# Sheet1.net
KiCad netlist of a schematic drawn in Altium Designer
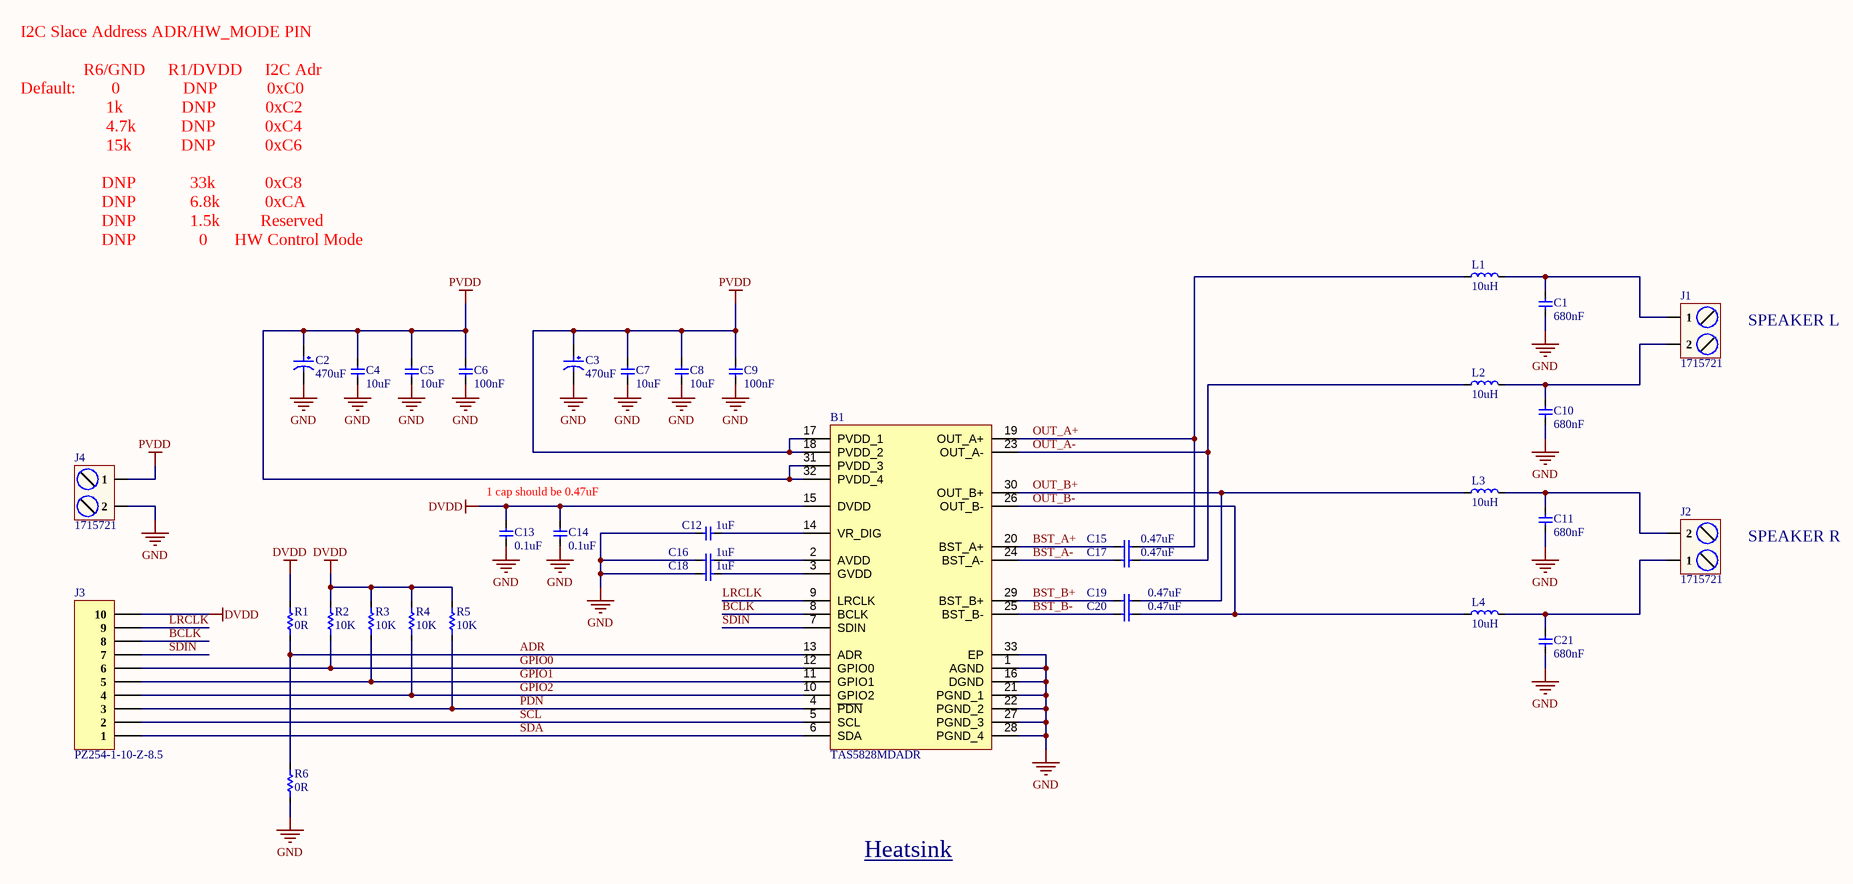
[diagram p0: Sheet1.SchDoc]

(export (version "E")
  (design (tool "Eeschema 10.0.6"))
  (components
    (comp (ref "B1")
      (value "TAS5828MDADR")
      (footprint "SOP65P810X115-33M")
      (fields
        (field (name "MOUSER PART NUMBER") "595-TAS5828MDADR")
        (field (name "LCSC PART NUMBER") "C5214953")
      )
      (libsource (lib "Schlib") (part "TAS5828MDADR"))
    )
    (comp (ref "C1")
      (value "680nF")
      (footprint "Cap-0805")
      (description "50V 680nF X7R ±10% 0805 Multilayer Ceramic Capacitors MLCC - SMD/SMT ROHS")
      (fields
        (field (name "MANUFACTURER") "YAGEO")
        (field (name "MANUFACTURER PART NUMBER") "CC0805KKX7R9BB684")
      )
      (libsource (lib "Schlib") (part "CC0805KKX7R9BB684"))
    )
    (comp (ref "C2")
      (value "470uF")
      (footprint "RVT470UF50V34RV0133")
      (description "470uF 50V 50mA@120Hz ±20% SMD,D12.5xL13.5mm Aluminum Electrolytic Capacitors - SMD ROHS")
      (fields (field (name "LCSC PART NUMBER") "C2837182") (field (name "MANUFACTURER") "KNSCHA"))
      (libsource (lib "Schlib") (part "RVT470UF50V34RV0133"))
    )
    (comp (ref "C3")
      (value "470uF")
      (footprint "RVT470UF50V34RV0133")
      (description "470uF 50V 50mA@120Hz ±20% SMD,D12.5xL13.5mm Aluminum Electrolytic Capacitors - SMD ROHS")
      (fields (field (name "LCSC PART NUMBER") "C2837182") (field (name "MANUFACTURER") "KNSCHA"))
      (libsource (lib "Schlib") (part "RVT470UF50V34RV0133"))
    )
    (comp (ref "C4")
      (value "10uF")
      (footprint "Cap-0805")
      (description "CAP CER 10UF 50V X5R 0805")
      (fields
        (field (name "MANUFACTURER") "Murata")
        (field (name "MANUFACTURER PART NUMBER") "GRM21BR61H106ME43L")
      )
      (libsource (lib "eSpark Libraries") (part "GRM21BR61H106ME43L"))
    )
    (comp (ref "C5")
      (value "10uF")
      (footprint "Cap-0805")
      (description "CAP CER 10UF 50V X5R 0805")
      (fields
        (field (name "MANUFACTURER") "Murata")
        (field (name "MANUFACTURER PART NUMBER") "GRM21BR61H106ME43L")
      )
      (libsource (lib "eSpark Libraries") (part "GRM21BR61H106ME43L"))
    )
    (comp (ref "C6")
      (value "100nF")
      (footprint "Cap-0603")
      (description "CAP CER 0.1UF 50V X5R 0603")
      (fields
        (field (name "MANUFACTURER") "Yageo")
        (field (name "MANUFACTURER PART NUMBER") "CC0603KRX5R9BB104")
      )
      (libsource (lib "Schlib") (part "CC0603KRX5R9BB104"))
    )
    (comp (ref "C7")
      (value "10uF")
      (footprint "Cap-0805")
      (description "CAP CER 10UF 50V X5R 0805")
      (fields
        (field (name "MANUFACTURER") "Murata")
        (field (name "MANUFACTURER PART NUMBER") "GRM21BR61H106ME43L")
      )
      (libsource (lib "eSpark Libraries") (part "GRM21BR61H106ME43L"))
    )
    (comp (ref "C8")
      (value "10uF")
      (footprint "Cap-0805")
      (description "CAP CER 10UF 50V X5R 0805")
      (fields
        (field (name "MANUFACTURER") "Murata")
        (field (name "MANUFACTURER PART NUMBER") "GRM21BR61H106ME43L")
      )
      (libsource (lib "eSpark Libraries") (part "GRM21BR61H106ME43L"))
    )
    (comp (ref "C9")
      (value "100nF")
      (footprint "Cap-0603")
      (description "CAP CER 0.1UF 50V X5R 0603")
      (fields
        (field (name "MANUFACTURER") "Yageo")
        (field (name "MANUFACTURER PART NUMBER") "CC0603KRX5R9BB104")
      )
      (libsource (lib "Schlib") (part "CC0603KRX5R9BB104"))
    )
    (comp (ref "C10")
      (value "680nF")
      (footprint "Cap-0805")
      (description "50V 680nF X7R ±10% 0805 Multilayer Ceramic Capacitors MLCC - SMD/SMT ROHS")
      (fields
        (field (name "MANUFACTURER") "YAGEO")
        (field (name "MANUFACTURER PART NUMBER") "CC0805KKX7R9BB684")
      )
      (libsource (lib "Schlib") (part "CC0805KKX7R9BB684"))
    )
    (comp (ref "C11")
      (value "680nF")
      (footprint "Cap-0805")
      (description "50V 680nF X7R ±10% 0805 Multilayer Ceramic Capacitors MLCC - SMD/SMT ROHS")
      (fields
        (field (name "MANUFACTURER") "YAGEO")
        (field (name "MANUFACTURER PART NUMBER") "CC0805KKX7R9BB684")
      )
      (libsource (lib "Schlib") (part "CC0805KKX7R9BB684"))
    )
    (comp (ref "C12")
      (value "1uF")
      (footprint "Cap-0603")
      (description "CAP CER 1UF 25V X5R 0603")
      (fields
        (field (name "MANUFACTURER") "Yageo")
        (field (name "MANUFACTURER PART NUMBER") "CC0603KRX5R8BB105")
      )
      (libsource (lib "Schlib") (part "CC0603KRX5R8BB105"))
    )
    (comp (ref "C13")
      (value "0.1uF")
      (footprint "Cap-0402")
      (description "CAP CER 0.1UF 16V X7R 0402")
      (fields
        (field (name "MANUFACTURER") "Yageo")
        (field (name "MANUFACTURER PART NUMBER") "CC0402JRX7R7BB104")
      )
      (libsource (lib "Schlib") (part "CC0402JRX7R7BB104"))
    )
    (comp (ref "C14")
      (value "0.1uF")
      (footprint "Cap-0402")
      (description "CAP CER 0.1UF 16V X7R 0402")
      (fields
        (field (name "MANUFACTURER") "Yageo")
        (field (name "MANUFACTURER PART NUMBER") "CC0402JRX7R7BB104")
      )
      (libsource (lib "Schlib") (part "CC0402JRX7R7BB104"))
    )
    (comp (ref "C15")
      (value "0.47uF")
      (footprint "Cap-0603")
      (description "CAP CER 0.47UF 50V X5R 0603")
      (fields
        (field (name "MANUFACTURER") "Yageo")
        (field (name "MANUFACTURER PART NUMBER") "CC0603KRX5R9BB474")
      )
      (libsource (lib "Schlib") (part "CC0603KRX5R9BB474"))
    )
    (comp (ref "C16")
      (value "1uF")
      (footprint "Cap-0603")
      (description "CAP CER 1UF 25V X5R 0603")
      (fields
        (field (name "MANUFACTURER") "Yageo")
        (field (name "MANUFACTURER PART NUMBER") "CC0603KRX5R8BB105")
      )
      (libsource (lib "Schlib") (part "CC0603KRX5R8BB105"))
    )
    (comp (ref "C17")
      (value "0.47uF")
      (footprint "Cap-0603")
      (description "CAP CER 0.47UF 50V X5R 0603")
      (fields
        (field (name "MANUFACTURER") "Yageo")
        (field (name "MANUFACTURER PART NUMBER") "CC0603KRX5R9BB474")
      )
      (libsource (lib "Schlib") (part "CC0603KRX5R9BB474"))
    )
    (comp (ref "C18")
      (value "1uF")
      (footprint "Cap-0603")
      (description "CAP CER 1UF 25V X5R 0603")
      (fields
        (field (name "MANUFACTURER") "Yageo")
        (field (name "MANUFACTURER PART NUMBER") "CC0603KRX5R8BB105")
      )
      (libsource (lib "Schlib") (part "CC0603KRX5R8BB105"))
    )
    (comp (ref "C19")
      (value "0.47uF")
      (footprint "Cap-0603")
      (description "CAP CER 0.47UF 50V X5R 0603")
      (fields
        (field (name "MANUFACTURER") "Yageo")
        (field (name "MANUFACTURER PART NUMBER") "CC0603KRX5R9BB474")
      )
      (libsource (lib "Schlib") (part "CC0603KRX5R9BB474"))
    )
    (comp (ref "C20")
      (value "0.47uF")
      (footprint "Cap-0603")
      (description "CAP CER 0.47UF 50V X5R 0603")
      (fields
        (field (name "MANUFACTURER") "Yageo")
        (field (name "MANUFACTURER PART NUMBER") "CC0603KRX5R9BB474")
      )
      (libsource (lib "Schlib") (part "CC0603KRX5R9BB474"))
    )
    (comp (ref "C21")
      (value "680nF")
      (footprint "Cap-0805")
      (description "50V 680nF X7R ±10% 0805 Multilayer Ceramic Capacitors MLCC - SMD/SMT ROHS")
      (fields
        (field (name "MANUFACTURER") "YAGEO")
        (field (name "MANUFACTURER PART NUMBER") "CC0805KKX7R9BB684")
      )
      (libsource (lib "Schlib") (part "CC0805KKX7R9BB684"))
    )
    (comp (ref "J1")
      (value "1715721")
      (footprint "1715721")
      (description "TERM BLK 2P SIDE ENT 5.08MM PCB")
      (fields (field (name "MANUFACTURER") "Phoenix Contact") (field (name "LCSC PART NUMBER") "C480516"))
      (libsource (lib "") (part "1715721_1"))
    )
    (comp (ref "J2")
      (value "1715721")
      (footprint "1715721")
      (description "TERM BLK 2P SIDE ENT 5.08MM PCB")
      (fields (field (name "MANUFACTURER") "Phoenix Contact") (field (name "LCSC PART NUMBER") "C480516"))
      (libsource (lib "Schlib") (part "1715721"))
    )
    (comp (ref "J3")
      (value "PZ254-1-10-Z-8.5")
      (footprint "PZ254-1-10-Z-8.5")
      (fields (field (name "MANUFACTURER") "HCTL") (field (name "LCSC PART NUMBER") "C2894933"))
      (libsource (lib "Schlib") (part "PZ254-1-10-Z-8.5"))
    )
    (comp (ref "J4")
      (value "1715721")
      (footprint "1715721")
      (description "TERM BLK 2P SIDE ENT 5.08MM PCB")
      (fields (field (name "MANUFACTURER") "Phoenix Contact") (field (name "LCSC PART NUMBER") "C480516"))
      (libsource (lib "") (part "1715721_2"))
    )
    (comp (ref "L1")
      (value "10uH")
      (footprint "PSPMAA1040-100M-ANP")
      (description "7A 10uH ±20% 10A SMD,10.3x10.5mm Power Inductors ROHS")
      (fields
        (field (name "MANUFACTURER") "PROD Tech")
        (field (name "MANUFACTURER PART NUMBER") "PSPMAA1040-100M-ANP")
      )
      (libsource (lib "Schlib") (part "PSPMAA1040-100M-ANP"))
    )
    (comp (ref "L2")
      (value "10uH")
      (footprint "PSPMAA1040-100M-ANP")
      (description "7A 10uH ±20% 10A SMD,10.3x10.5mm Power Inductors ROHS")
      (fields
        (field (name "MANUFACTURER") "PROD Tech")
        (field (name "MANUFACTURER PART NUMBER") "PSPMAA1040-100M-ANP")
      )
      (libsource (lib "Schlib") (part "PSPMAA1040-100M-ANP"))
    )
    (comp (ref "L3")
      (value "10uH")
      (footprint "PSPMAA1040-100M-ANP")
      (description "7A 10uH ±20% 10A SMD,10.3x10.5mm Power Inductors ROHS")
      (fields
        (field (name "MANUFACTURER") "PROD Tech")
        (field (name "MANUFACTURER PART NUMBER") "PSPMAA1040-100M-ANP")
      )
      (libsource (lib "Schlib") (part "PSPMAA1040-100M-ANP"))
    )
    (comp (ref "L4")
      (value "10uH")
      (footprint "PSPMAA1040-100M-ANP")
      (description "7A 10uH ±20% 10A SMD,10.3x10.5mm Power Inductors ROHS")
      (fields
        (field (name "MANUFACTURER") "PROD Tech")
        (field (name "MANUFACTURER PART NUMBER") "PSPMAA1040-100M-ANP")
      )
      (libsource (lib "Schlib") (part "PSPMAA1040-100M-ANP"))
    )
    (comp (ref "R1")
      (value "0R")
      (footprint "Res-0402")
      (description "RES 0 OHM JUMPER 1/16W 0402")
      (fields
        (field (name "MANUFACTURER") "Yageo")
        (field (name "MANUFACTURER PART NUMBER") "RC0402FR-070RL")
      )
      (libsource (lib "Schlib") (part "RC0402FR-070RL"))
    )
    (comp (ref "R2")
      (value "10K")
      (footprint "Res-0402")
      (description "RES 10K OHM 1% 1/16W 0402")
      (fields
        (field (name "MANUFACTURER") "Yageo")
        (field (name "MANUFACTURER PART NUMBER") "RC0402FR-0710KL")
      )
      (libsource (lib "Schlib") (part "RC0402FR-0710KL"))
    )
    (comp (ref "R3")
      (value "10K")
      (footprint "Res-0402")
      (description "RES 10K OHM 1% 1/16W 0402")
      (fields
        (field (name "MANUFACTURER") "Yageo")
        (field (name "MANUFACTURER PART NUMBER") "RC0402FR-0710KL")
      )
      (libsource (lib "Schlib") (part "RC0402FR-0710KL"))
    )
    (comp (ref "R4")
      (value "10K")
      (footprint "Res-0402")
      (description "RES 10K OHM 1% 1/16W 0402")
      (fields
        (field (name "MANUFACTURER") "Yageo")
        (field (name "MANUFACTURER PART NUMBER") "RC0402FR-0710KL")
      )
      (libsource (lib "Schlib") (part "RC0402FR-0710KL"))
    )
    (comp (ref "R5")
      (value "10K")
      (footprint "Res-0402")
      (description "RES 10K OHM 1% 1/16W 0402")
      (fields
        (field (name "MANUFACTURER") "Yageo")
        (field (name "MANUFACTURER PART NUMBER") "RC0402FR-0710KL")
      )
      (libsource (lib "Schlib") (part "RC0402FR-0710KL"))
    )
    (comp (ref "R6")
      (value "0R")
      (footprint "Res-0402")
      (description "RES 0 OHM JUMPER 1/16W 0402")
      (fields
        (field (name "MANUFACTURER") "Yageo")
        (field (name "MANUFACTURER PART NUMBER") "RC0402FR-070RL")
      )
      (libsource (lib "Schlib") (part "RC0402FR-070RL"))
    )
  )
  (nets
    (net (code "1") (name "/ADR") (class "Default")
      (node (ref "B1") (pin "13") (pinfunction "ADR_13") (pintype "passive"))
      (node (ref "R1") (pin "1") (pinfunction "1_1") (pintype "passive"))
      (node (ref "R6") (pin "2") (pinfunction "2_2") (pintype "passive"))
    )
    (net (code "2") (name "/BCLK") (class "Default")
      (node (ref "B1") (pin "8") (pinfunction "BCLK_8") (pintype "passive"))
      (node (ref "J3") (pin "8") (pinfunction "8_8") (pintype "passive"))
    )
    (net (code "3") (name "/BST_A+") (class "Default")
      (node (ref "B1") (pin "20") (pinfunction "BST_A+_20") (pintype "passive"))
      (node (ref "C15") (pin "1") (pinfunction "1_1") (pintype "passive"))
    )
    (net (code "4") (name "/BST_A-") (class "Default")
      (node (ref "B1") (pin "24") (pinfunction "BST_A-_24") (pintype "passive"))
      (node (ref "C17") (pin "1") (pinfunction "1_1") (pintype "passive"))
    )
    (net (code "5") (name "/BST_B+") (class "Default")
      (node (ref "B1") (pin "29") (pinfunction "BST_B+_29") (pintype "passive"))
      (node (ref "C19") (pin "1") (pinfunction "1_1") (pintype "passive"))
    )
    (net (code "6") (name "/BST_B-") (class "Default")
      (node (ref "B1") (pin "25") (pinfunction "BST_B-_25") (pintype "passive"))
      (node (ref "C20") (pin "1") (pinfunction "1_1") (pintype "passive"))
    )
    (net (code "7") (name "/GPIO0") (class "Default")
      (node (ref "B1") (pin "12") (pinfunction "GPIO0_12") (pintype "passive"))
      (node (ref "J3") (pin "6") (pinfunction "6_6") (pintype "passive"))
      (node (ref "R2") (pin "1") (pinfunction "1_1") (pintype "passive"))
    )
    (net (code "8") (name "/GPIO1") (class "Default")
      (node (ref "B1") (pin "11") (pinfunction "GPIO1_11") (pintype "passive"))
      (node (ref "J3") (pin "5") (pinfunction "5_5") (pintype "passive"))
      (node (ref "R3") (pin "1") (pinfunction "1_1") (pintype "passive"))
    )
    (net (code "9") (name "/GPIO2") (class "Default")
      (node (ref "B1") (pin "10") (pinfunction "GPIO2_10") (pintype "passive"))
      (node (ref "J3") (pin "4") (pinfunction "4_4") (pintype "passive"))
      (node (ref "R4") (pin "1") (pinfunction "1_1") (pintype "passive"))
    )
    (net (code "10") (name "/LRCLK") (class "Default")
      (node (ref "B1") (pin "9") (pinfunction "LRCLK_9") (pintype "passive"))
      (node (ref "J3") (pin "9") (pinfunction "9_9") (pintype "passive"))
    )
    (net (code "11") (name "/OUT_A+") (class "Default")
      (node (ref "B1") (pin "19") (pinfunction "OUT_A+_19") (pintype "passive"))
      (node (ref "C15") (pin "2") (pinfunction "2_2") (pintype "passive"))
      (node (ref "L1") (pin "1") (pinfunction "1_1") (pintype "passive"))
    )
    (net (code "12") (name "/OUT_A-") (class "Default")
      (node (ref "B1") (pin "23") (pinfunction "OUT_A-_23") (pintype "passive"))
      (node (ref "C17") (pin "2") (pinfunction "2_2") (pintype "passive"))
      (node (ref "L2") (pin "1") (pinfunction "1_1") (pintype "passive"))
    )
    (net (code "13") (name "/OUT_B+") (class "Default")
      (node (ref "B1") (pin "30") (pinfunction "OUT_B+_30") (pintype "passive"))
      (node (ref "C19") (pin "2") (pinfunction "2_2") (pintype "passive"))
      (node (ref "L3") (pin "1") (pinfunction "1_1") (pintype "passive"))
    )
    (net (code "14") (name "/OUT_B-") (class "Default")
      (node (ref "B1") (pin "26") (pinfunction "OUT_B-_26") (pintype "passive"))
      (node (ref "C20") (pin "2") (pinfunction "2_2") (pintype "passive"))
      (node (ref "L4") (pin "1") (pinfunction "1_1") (pintype "passive"))
    )
    (net (code "15") (name "/PDN") (class "Default")
      (node (ref "B1") (pin "4") (pinfunction "~{PDN}_4") (pintype "passive"))
      (node (ref "J3") (pin "3") (pinfunction "3_3") (pintype "passive"))
      (node (ref "R5") (pin "1") (pinfunction "1_1") (pintype "passive"))
    )
    (net (code "16") (name "/SCL") (class "Default")
      (node (ref "B1") (pin "5") (pinfunction "SCL_5") (pintype "passive"))
      (node (ref "J3") (pin "2") (pinfunction "2_2") (pintype "passive"))
    )
    (net (code "17") (name "/SDA") (class "Default")
      (node (ref "B1") (pin "6") (pinfunction "SDA_6") (pintype "passive"))
      (node (ref "J3") (pin "1") (pinfunction "1_1") (pintype "passive"))
    )
    (net (code "18") (name "/SDIN") (class "Default")
      (node (ref "B1") (pin "7") (pinfunction "SDIN_7") (pintype "passive"))
      (node (ref "J3") (pin "7") (pinfunction "7_7") (pintype "passive"))
    )
    (net (code "19") (name "DVDD") (class "Default")
      (node (ref "B1") (pin "15") (pinfunction "DVDD_15") (pintype "passive"))
      (node (ref "C13") (pin "2") (pinfunction "2_2") (pintype "passive"))
      (node (ref "C14") (pin "2") (pinfunction "2_2") (pintype "passive"))
      (node (ref "J3") (pin "10") (pinfunction "10_10") (pintype "passive"))
      (node (ref "R1") (pin "2") (pinfunction "2_2") (pintype "passive"))
      (node (ref "R2") (pin "2") (pinfunction "2_2") (pintype "passive"))
      (node (ref "R3") (pin "2") (pinfunction "2_2") (pintype "passive"))
      (node (ref "R4") (pin "2") (pinfunction "2_2") (pintype "passive"))
      (node (ref "R5") (pin "2") (pinfunction "2_2") (pintype "passive"))
    )
    (net (code "20") (name "GND") (class "Default")
      (node (ref "B1") (pin "1") (pinfunction "AGND_1") (pintype "passive"))
      (node (ref "B1") (pin "16") (pinfunction "DGND_16") (pintype "passive"))
      (node (ref "B1") (pin "21") (pinfunction "PGND_1_21") (pintype "passive"))
      (node (ref "B1") (pin "22") (pinfunction "PGND_2_22") (pintype "passive"))
      (node (ref "B1") (pin "27") (pinfunction "PGND_3_27") (pintype "passive"))
      (node (ref "B1") (pin "28") (pinfunction "PGND_4_28") (pintype "passive"))
      (node (ref "B1") (pin "33") (pinfunction "EP_33") (pintype "passive"))
      (node (ref "C1") (pin "1") (pinfunction "1_1") (pintype "passive"))
      (node (ref "C10") (pin "1") (pinfunction "1_1") (pintype "passive"))
      (node (ref "C11") (pin "1") (pinfunction "1_1") (pintype "passive"))
      (node (ref "C12") (pin "1") (pinfunction "1_1") (pintype "passive"))
      (node (ref "C13") (pin "1") (pinfunction "1_1") (pintype "passive"))
      (node (ref "C14") (pin "1") (pinfunction "1_1") (pintype "passive"))
      (node (ref "C16") (pin "1") (pinfunction "1_1") (pintype "passive"))
      (node (ref "C18") (pin "1") (pinfunction "1_1") (pintype "passive"))
      (node (ref "C2") (pin "2") (pintype "passive"))
      (node (ref "C21") (pin "1") (pinfunction "1_1") (pintype "passive"))
      (node (ref "C3") (pin "2") (pintype "passive"))
      (node (ref "C4") (pin "1") (pinfunction "1_1") (pintype "passive"))
      (node (ref "C5") (pin "1") (pinfunction "1_1") (pintype "passive"))
      (node (ref "C6") (pin "1") (pinfunction "1_1") (pintype "passive"))
      (node (ref "C7") (pin "1") (pinfunction "1_1") (pintype "passive"))
      (node (ref "C8") (pin "1") (pinfunction "1_1") (pintype "passive"))
      (node (ref "C9") (pin "1") (pinfunction "1_1") (pintype "passive"))
      (node (ref "J4") (pin "2") (pinfunction "2_2") (pintype "passive"))
      (node (ref "R6") (pin "1") (pinfunction "1_1") (pintype "passive"))
    )
    (net (code "21") (name "Net-(B1-AVDD)") (class "Default")
      (node (ref "B1") (pin "2") (pinfunction "AVDD_2") (pintype "passive"))
      (node (ref "C16") (pin "2") (pinfunction "2_2") (pintype "passive"))
    )
    (net (code "22") (name "Net-(B1-GVDD)") (class "Default")
      (node (ref "B1") (pin "3") (pinfunction "GVDD_3") (pintype "passive"))
      (node (ref "C18") (pin "2") (pinfunction "2_2") (pintype "passive"))
    )
    (net (code "23") (name "Net-(B1-VR_DIG)") (class "Default")
      (node (ref "B1") (pin "14") (pinfunction "VR_DIG_14") (pintype "passive"))
      (node (ref "C12") (pin "2") (pinfunction "2_2") (pintype "passive"))
    )
    (net (code "24") (name "Net-(C1-Pad2)") (class "Default")
      (node (ref "C1") (pin "2") (pinfunction "2_2") (pintype "passive"))
      (node (ref "J1") (pin "1") (pinfunction "1_1") (pintype "passive"))
      (node (ref "L1") (pin "2") (pinfunction "2_2") (pintype "passive"))
    )
    (net (code "25") (name "Net-(C10-Pad2)") (class "Default")
      (node (ref "C10") (pin "2") (pinfunction "2_2") (pintype "passive"))
      (node (ref "J1") (pin "2") (pinfunction "2_2") (pintype "passive"))
      (node (ref "L2") (pin "2") (pinfunction "2_2") (pintype "passive"))
    )
    (net (code "26") (name "Net-(C11-Pad2)") (class "Default")
      (node (ref "C11") (pin "2") (pinfunction "2_2") (pintype "passive"))
      (node (ref "J2") (pin "2") (pinfunction "2_2") (pintype "passive"))
      (node (ref "L3") (pin "2") (pinfunction "2_2") (pintype "passive"))
    )
    (net (code "27") (name "Net-(C21-Pad2)") (class "Default")
      (node (ref "C21") (pin "2") (pinfunction "2_2") (pintype "passive"))
      (node (ref "J2") (pin "1") (pinfunction "1_1") (pintype "passive"))
      (node (ref "L4") (pin "2") (pinfunction "2_2") (pintype "passive"))
    )
    (net (code "28") (name "PVDD") (class "Default")
      (node (ref "B1") (pin "17") (pinfunction "PVDD_1_17") (pintype "passive"))
      (node (ref "B1") (pin "18") (pinfunction "PVDD_2_18") (pintype "passive"))
      (node (ref "B1") (pin "31") (pinfunction "PVDD_3_31") (pintype "passive"))
      (node (ref "B1") (pin "32") (pinfunction "PVDD_4_32") (pintype "passive"))
      (node (ref "C2") (pin "1") (pintype "passive"))
      (node (ref "C3") (pin "1") (pintype "passive"))
      (node (ref "C4") (pin "2") (pinfunction "2_2") (pintype "passive"))
      (node (ref "C5") (pin "2") (pinfunction "2_2") (pintype "passive"))
      (node (ref "C6") (pin "2") (pinfunction "2_2") (pintype "passive"))
      (node (ref "C7") (pin "2") (pinfunction "2_2") (pintype "passive"))
      (node (ref "C8") (pin "2") (pinfunction "2_2") (pintype "passive"))
      (node (ref "C9") (pin "2") (pinfunction "2_2") (pintype "passive"))
      (node (ref "J4") (pin "1") (pinfunction "1_1") (pintype "passive"))
    )
  )
)
